# umodular_iface8_rev01.net
KiCad netlist of a schematic drawn in EAGLE
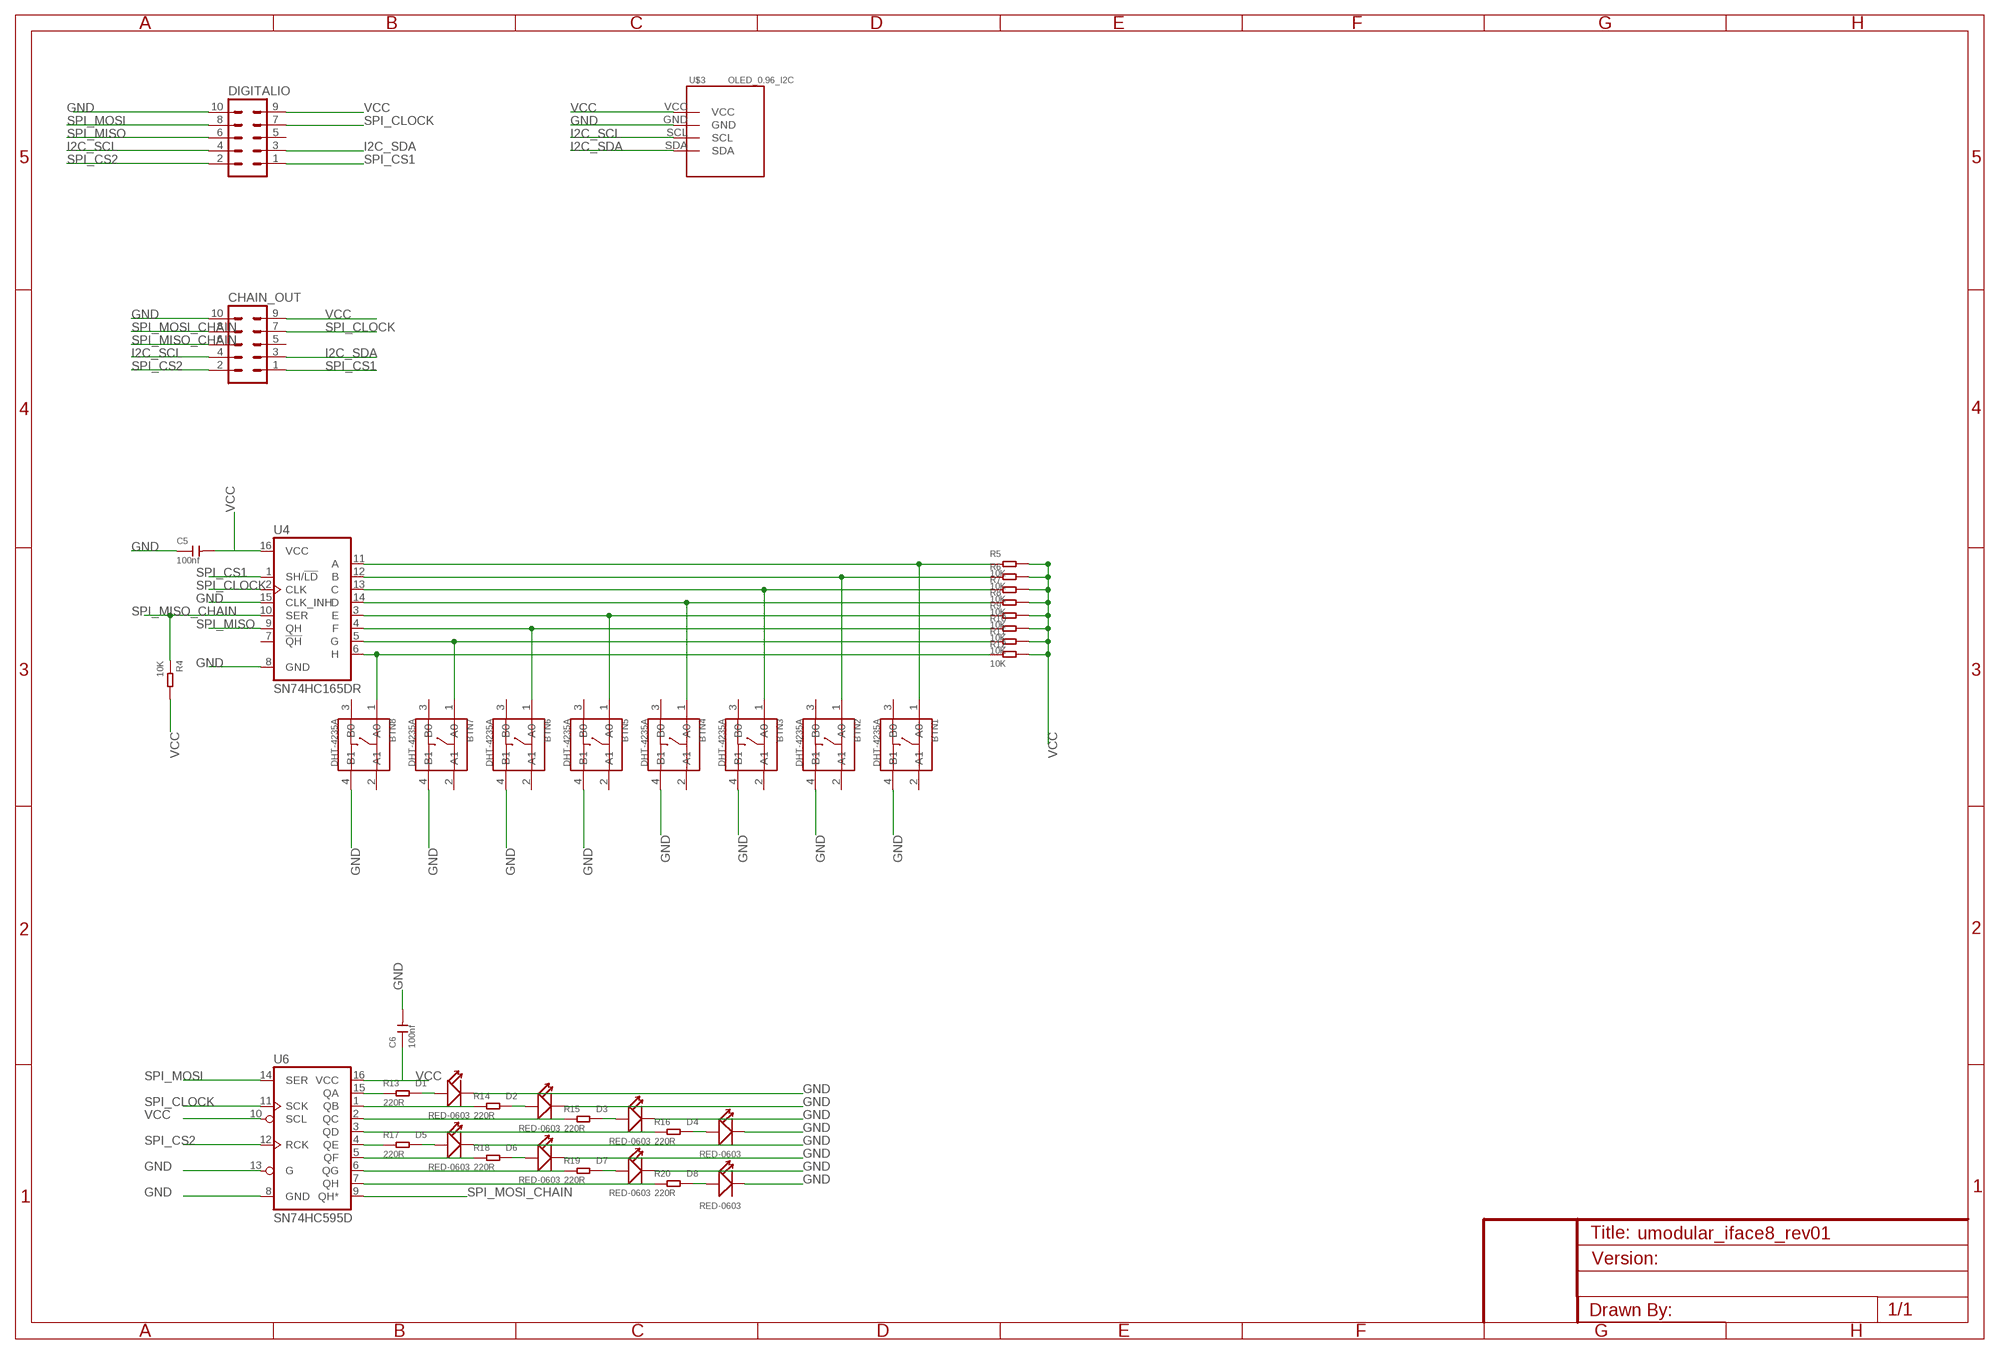
[diagram p0: schematic, sheet 1]

(export (version "E")
  (design (tool "Eeschema 10.0.6"))
  (components
    (comp (ref "BTN1")
      (value "DHT-4235A")
      (footprint "eagle-import:SW4-SMD-4.2X3.2X2.5MM")
      (libsource (lib "eagle-import") (part "SMD-BUTTON-TOP-DHT-4235A(4P-4.2X3.2MM)"))
    )
    (comp (ref "BTN2")
      (value "DHT-4235A")
      (footprint "eagle-import:SW4-SMD-4.2X3.2X2.5MM")
      (libsource (lib "eagle-import") (part "SMD-BUTTON-TOP-DHT-4235A(4P-4.2X3.2MM)"))
    )
    (comp (ref "BTN3")
      (value "DHT-4235A")
      (footprint "eagle-import:SW4-SMD-4.2X3.2X2.5MM")
      (libsource (lib "eagle-import") (part "SMD-BUTTON-TOP-DHT-4235A(4P-4.2X3.2MM)"))
    )
    (comp (ref "BTN4")
      (value "DHT-4235A")
      (footprint "eagle-import:SW4-SMD-4.2X3.2X2.5MM")
      (libsource (lib "eagle-import") (part "SMD-BUTTON-TOP-DHT-4235A(4P-4.2X3.2MM)"))
    )
    (comp (ref "BTN5")
      (value "DHT-4235A")
      (footprint "eagle-import:SW4-SMD-4.2X3.2X2.5MM")
      (libsource (lib "eagle-import") (part "SMD-BUTTON-TOP-DHT-4235A(4P-4.2X3.2MM)"))
    )
    (comp (ref "BTN6")
      (value "DHT-4235A")
      (footprint "eagle-import:SW4-SMD-4.2X3.2X2.5MM")
      (libsource (lib "eagle-import") (part "SMD-BUTTON-TOP-DHT-4235A(4P-4.2X3.2MM)"))
    )
    (comp (ref "BTN7")
      (value "DHT-4235A")
      (footprint "eagle-import:SW4-SMD-4.2X3.2X2.5MM")
      (libsource (lib "eagle-import") (part "SMD-BUTTON-TOP-DHT-4235A(4P-4.2X3.2MM)"))
    )
    (comp (ref "BTN8")
      (value "DHT-4235A")
      (footprint "eagle-import:SW4-SMD-4.2X3.2X2.5MM")
      (libsource (lib "eagle-import") (part "SMD-BUTTON-TOP-DHT-4235A(4P-4.2X3.2MM)"))
    )
    (comp (ref "C5")
      (value "100nf")
      (footprint "eagle-import:C0805")
      (fields (field (name "MPN") "CC0805KRX7R9BB104"))
      (libsource (lib "eagle-import") (part "CERAMIC-100NF-50V-10%-X7R(0805)"))
    )
    (comp (ref "C6")
      (value "100nf")
      (footprint "eagle-import:C0805")
      (fields (field (name "MPN") "CC0805KRX7R9BB104"))
      (libsource (lib "eagle-import") (part "CERAMIC-100NF-50V-10%-X7R(0805)"))
    )
    (comp (ref "CHAIN_OUT")
      (value "MA05-2")
      (footprint "eagle-import:MA05-2")
      (libsource (lib "eagle-import") (part "MA05-2"))
    )
    (comp (ref "D1")
      (value "RED-0603")
      (footprint "eagle-import:LED-0603")
      (fields (field (name "MPN") "19-217-R6C-AL1M2VY-3T"))
      (libsource (lib "eagle-import") (part "LED-SMD-RED-DIFFUSED(0603)"))
    )
    (comp (ref "D2")
      (value "RED-0603")
      (footprint "eagle-import:LED-0603")
      (fields (field (name "MPN") "19-217-R6C-AL1M2VY-3T"))
      (libsource (lib "eagle-import") (part "LED-SMD-RED-DIFFUSED(0603)"))
    )
    (comp (ref "D3")
      (value "RED-0603")
      (footprint "eagle-import:LED-0603")
      (fields (field (name "MPN") "19-217-R6C-AL1M2VY-3T"))
      (libsource (lib "eagle-import") (part "LED-SMD-RED-DIFFUSED(0603)"))
    )
    (comp (ref "D4")
      (value "RED-0603")
      (footprint "eagle-import:LED-0603")
      (fields (field (name "MPN") "19-217-R6C-AL1M2VY-3T"))
      (libsource (lib "eagle-import") (part "LED-SMD-RED-DIFFUSED(0603)"))
    )
    (comp (ref "D5")
      (value "RED-0603")
      (footprint "eagle-import:LED-0603")
      (fields (field (name "MPN") "19-217-R6C-AL1M2VY-3T"))
      (libsource (lib "eagle-import") (part "LED-SMD-RED-DIFFUSED(0603)"))
    )
    (comp (ref "D6")
      (value "RED-0603")
      (footprint "eagle-import:LED-0603")
      (fields (field (name "MPN") "19-217-R6C-AL1M2VY-3T"))
      (libsource (lib "eagle-import") (part "LED-SMD-RED-DIFFUSED(0603)"))
    )
    (comp (ref "D7")
      (value "RED-0603")
      (footprint "eagle-import:LED-0603")
      (fields (field (name "MPN") "19-217-R6C-AL1M2VY-3T"))
      (libsource (lib "eagle-import") (part "LED-SMD-RED-DIFFUSED(0603)"))
    )
    (comp (ref "D8")
      (value "RED-0603")
      (footprint "eagle-import:LED-0603")
      (fields (field (name "MPN") "19-217-R6C-AL1M2VY-3T"))
      (libsource (lib "eagle-import") (part "LED-SMD-RED-DIFFUSED(0603)"))
    )
    (comp (ref "DIGITALIO")
      (value "MA05-2")
      (footprint "eagle-import:MA05-2")
      (libsource (lib "eagle-import") (part "MA05-2"))
    )
    (comp (ref "R4")
      (value "10K")
      (footprint "eagle-import:R0603")
      (fields (field (name "MPN") "RC0603JR-0710KL"))
      (libsource (lib "eagle-import") (part "SMD-RES-10K-5%-1/10W(0603)"))
    )
    (comp (ref "R5")
      (value "10K")
      (footprint "eagle-import:R0603")
      (fields (field (name "MPN") "RC0603JR-0710KL"))
      (libsource (lib "eagle-import") (part "SMD-RES-10K-5%-1/10W(0603)"))
    )
    (comp (ref "R6")
      (value "10K")
      (footprint "eagle-import:R0603")
      (fields (field (name "MPN") "RC0603JR-0710KL"))
      (libsource (lib "eagle-import") (part "SMD-RES-10K-5%-1/10W(0603)"))
    )
    (comp (ref "R7")
      (value "10K")
      (footprint "eagle-import:R0603")
      (fields (field (name "MPN") "RC0603JR-0710KL"))
      (libsource (lib "eagle-import") (part "SMD-RES-10K-5%-1/10W(0603)"))
    )
    (comp (ref "R8")
      (value "10K")
      (footprint "eagle-import:R0603")
      (fields (field (name "MPN") "RC0603JR-0710KL"))
      (libsource (lib "eagle-import") (part "SMD-RES-10K-5%-1/10W(0603)"))
    )
    (comp (ref "R9")
      (value "10K")
      (footprint "eagle-import:R0603")
      (fields (field (name "MPN") "RC0603JR-0710KL"))
      (libsource (lib "eagle-import") (part "SMD-RES-10K-5%-1/10W(0603)"))
    )
    (comp (ref "R10")
      (value "10K")
      (footprint "eagle-import:R0603")
      (fields (field (name "MPN") "RC0603JR-0710KL"))
      (libsource (lib "eagle-import") (part "SMD-RES-10K-5%-1/10W(0603)"))
    )
    (comp (ref "R11")
      (value "10K")
      (footprint "eagle-import:R0603")
      (fields (field (name "MPN") "RC0603JR-0710KL"))
      (libsource (lib "eagle-import") (part "SMD-RES-10K-5%-1/10W(0603)"))
    )
    (comp (ref "R12")
      (value "10K")
      (footprint "eagle-import:R0603")
      (fields (field (name "MPN") "RC0603JR-0710KL"))
      (libsource (lib "eagle-import") (part "SMD-RES-10K-5%-1/10W(0603)"))
    )
    (comp (ref "R13")
      (value "220R")
      (footprint "eagle-import:R0603")
      (fields (field (name "MPN") "RC0603JR-07220RL"))
      (libsource (lib "eagle-import") (part "SMD-RES-220R-5%-1/10W(0603)"))
    )
    (comp (ref "R14")
      (value "220R")
      (footprint "eagle-import:R0603")
      (fields (field (name "MPN") "RC0603JR-07220RL"))
      (libsource (lib "eagle-import") (part "SMD-RES-220R-5%-1/10W(0603)"))
    )
    (comp (ref "R15")
      (value "220R")
      (footprint "eagle-import:R0603")
      (fields (field (name "MPN") "RC0603JR-07220RL"))
      (libsource (lib "eagle-import") (part "SMD-RES-220R-5%-1/10W(0603)"))
    )
    (comp (ref "R16")
      (value "220R")
      (footprint "eagle-import:R0603")
      (fields (field (name "MPN") "RC0603JR-07220RL"))
      (libsource (lib "eagle-import") (part "SMD-RES-220R-5%-1/10W(0603)"))
    )
    (comp (ref "R17")
      (value "220R")
      (footprint "eagle-import:R0603")
      (fields (field (name "MPN") "RC0603JR-07220RL"))
      (libsource (lib "eagle-import") (part "SMD-RES-220R-5%-1/10W(0603)"))
    )
    (comp (ref "R18")
      (value "220R")
      (footprint "eagle-import:R0603")
      (fields (field (name "MPN") "RC0603JR-07220RL"))
      (libsource (lib "eagle-import") (part "SMD-RES-220R-5%-1/10W(0603)"))
    )
    (comp (ref "R19")
      (value "220R")
      (footprint "eagle-import:R0603")
      (fields (field (name "MPN") "RC0603JR-07220RL"))
      (libsource (lib "eagle-import") (part "SMD-RES-220R-5%-1/10W(0603)"))
    )
    (comp (ref "R20")
      (value "220R")
      (footprint "eagle-import:R0603")
      (fields (field (name "MPN") "RC0603JR-07220RL"))
      (libsource (lib "eagle-import") (part "SMD-RES-220R-5%-1/10W(0603)"))
    )
    (comp (ref "U$3")
      (value "OLED_0.96_I2C")
      (footprint "eagle-import:OLED_0.96_I2C")
      (libsource (lib "eagle-import") (part "OLED_0.96_I2C"))
    )
    (comp (ref "U4")
      (value "SN74HC165DR")
      (footprint "eagle-import:SO16")
      (libsource (lib "eagle-import") (part "74165DHC"))
    )
    (comp (ref "U6")
      (value "SN74HC595D")
      (footprint "eagle-import:SO16")
      (libsource (lib "eagle-import") (part "74595DHC"))
    )
  )
  (nets
    (net (code "1") (name "/GND") (class "Default")
      (node (ref "BTN1") (pin "4") (pinfunction "B1_4") (pintype "bidirectional"))
      (node (ref "BTN2") (pin "4") (pinfunction "B1_4") (pintype "bidirectional"))
      (node (ref "BTN3") (pin "4") (pinfunction "B1_4") (pintype "bidirectional"))
      (node (ref "BTN4") (pin "4") (pinfunction "B1_4") (pintype "bidirectional"))
      (node (ref "BTN5") (pin "4") (pinfunction "B1_4") (pintype "bidirectional"))
      (node (ref "BTN6") (pin "4") (pinfunction "B1_4") (pintype "bidirectional"))
      (node (ref "BTN7") (pin "4") (pinfunction "B1_4") (pintype "bidirectional"))
      (node (ref "BTN8") (pin "4") (pinfunction "B1_4") (pintype "bidirectional"))
      (node (ref "C5") (pin "1") (pinfunction "1_1") (pintype "passive"))
      (node (ref "C6") (pin "2") (pinfunction "2_2") (pintype "passive"))
      (node (ref "CHAIN_OUT") (pin "10") (pinfunction "10_10") (pintype "passive"))
      (node (ref "D1") (pin "-") (pinfunction "-_-") (pintype "passive"))
      (node (ref "D2") (pin "-") (pinfunction "-_-") (pintype "passive"))
      (node (ref "D3") (pin "-") (pinfunction "-_-") (pintype "passive"))
      (node (ref "D4") (pin "-") (pinfunction "-_-") (pintype "passive"))
      (node (ref "D5") (pin "-") (pinfunction "-_-") (pintype "passive"))
      (node (ref "D6") (pin "-") (pinfunction "-_-") (pintype "passive"))
      (node (ref "D7") (pin "-") (pinfunction "-_-") (pintype "passive"))
      (node (ref "D8") (pin "-") (pinfunction "-_-") (pintype "passive"))
      (node (ref "DIGITALIO") (pin "10") (pinfunction "10_10") (pintype "passive"))
      (node (ref "U$3") (pin "GND") (pinfunction "GND_GND") (pintype "bidirectional"))
      (node (ref "U4") (pin "15") (pinfunction "CLK_INH_15") (pintype "input"))
      (node (ref "U4") (pin "8") (pinfunction "GND_8") (pintype "power_in"))
      (node (ref "U6") (pin "13") (pinfunction "G_13") (pintype "input"))
      (node (ref "U6") (pin "8") (pinfunction "GND_8") (pintype "power_in"))
    )
    (net (code "2") (name "/I2C_SCL") (class "Default")
      (node (ref "CHAIN_OUT") (pin "4") (pinfunction "4_4") (pintype "passive"))
      (node (ref "DIGITALIO") (pin "4") (pinfunction "4_4") (pintype "passive"))
      (node (ref "U$3") (pin "SCL") (pinfunction "SCL_SCL") (pintype "bidirectional"))
    )
    (net (code "3") (name "/I2C_SDA") (class "Default")
      (node (ref "CHAIN_OUT") (pin "3") (pinfunction "3_3") (pintype "passive"))
      (node (ref "DIGITALIO") (pin "3") (pinfunction "3_3") (pintype "passive"))
      (node (ref "U$3") (pin "SDA") (pinfunction "SDA_SDA") (pintype "bidirectional"))
    )
    (net (code "4") (name "/SPI_CLOCK") (class "Default")
      (node (ref "CHAIN_OUT") (pin "7") (pinfunction "7_7") (pintype "passive"))
      (node (ref "DIGITALIO") (pin "7") (pinfunction "7_7") (pintype "passive"))
      (node (ref "U4") (pin "2") (pinfunction "CLK_2") (pintype "input"))
      (node (ref "U6") (pin "11") (pinfunction "SCK_11") (pintype "input"))
    )
    (net (code "5") (name "/SPI_CS1") (class "Default")
      (node (ref "CHAIN_OUT") (pin "1") (pinfunction "1_1") (pintype "passive"))
      (node (ref "DIGITALIO") (pin "1") (pinfunction "1_1") (pintype "passive"))
      (node (ref "U4") (pin "1") (pinfunction "SH/~{LD}_1") (pintype "input"))
    )
    (net (code "6") (name "/SPI_CS2") (class "Default")
      (node (ref "CHAIN_OUT") (pin "2") (pinfunction "2_2") (pintype "passive"))
      (node (ref "DIGITALIO") (pin "2") (pinfunction "2_2") (pintype "passive"))
      (node (ref "U6") (pin "12") (pinfunction "RCK_12") (pintype "input"))
    )
    (net (code "7") (name "/SPI_MISO") (class "Default")
      (node (ref "DIGITALIO") (pin "6") (pinfunction "6_6") (pintype "passive"))
      (node (ref "U4") (pin "9") (pinfunction "QH_9") (pintype "tri_state"))
    )
    (net (code "8") (name "/SPI_MISO_CHAIN") (class "Default")
      (node (ref "CHAIN_OUT") (pin "6") (pinfunction "6_6") (pintype "passive"))
      (node (ref "R4") (pin "1") (pinfunction "1_1") (pintype "passive"))
      (node (ref "U4") (pin "10") (pinfunction "SER_10") (pintype "input"))
    )
    (net (code "9") (name "/SPI_MOSI") (class "Default")
      (node (ref "DIGITALIO") (pin "8") (pinfunction "8_8") (pintype "passive"))
      (node (ref "U6") (pin "14") (pinfunction "SER_14") (pintype "input"))
    )
    (net (code "10") (name "/SPI_MOSI_CHAIN") (class "Default")
      (node (ref "CHAIN_OUT") (pin "8") (pinfunction "8_8") (pintype "passive"))
      (node (ref "U6") (pin "9") (pinfunction "QH*_9") (pintype "tri_state"))
    )
    (net (code "11") (name "/VCC") (class "Default")
      (node (ref "C5") (pin "2") (pinfunction "2_2") (pintype "passive"))
      (node (ref "C6") (pin "1") (pinfunction "1_1") (pintype "passive"))
      (node (ref "CHAIN_OUT") (pin "9") (pinfunction "9_9") (pintype "passive"))
      (node (ref "DIGITALIO") (pin "9") (pinfunction "9_9") (pintype "passive"))
      (node (ref "R10") (pin "2") (pinfunction "2_2") (pintype "passive"))
      (node (ref "R11") (pin "2") (pinfunction "2_2") (pintype "passive"))
      (node (ref "R12") (pin "2") (pinfunction "2_2") (pintype "passive"))
      (node (ref "R4") (pin "2") (pinfunction "2_2") (pintype "passive"))
      (node (ref "R5") (pin "2") (pinfunction "2_2") (pintype "passive"))
      (node (ref "R6") (pin "2") (pinfunction "2_2") (pintype "passive"))
      (node (ref "R7") (pin "2") (pinfunction "2_2") (pintype "passive"))
      (node (ref "R8") (pin "2") (pinfunction "2_2") (pintype "passive"))
      (node (ref "R9") (pin "2") (pinfunction "2_2") (pintype "passive"))
      (node (ref "U$3") (pin "VCC") (pinfunction "VCC_VCC") (pintype "bidirectional"))
      (node (ref "U4") (pin "16") (pinfunction "VCC_16") (pintype "power_in"))
      (node (ref "U6") (pin "10") (pinfunction "SCL_10") (pintype "input"))
      (node (ref "U6") (pin "16") (pinfunction "VCC_16") (pintype "power_in"))
    )
    (net (code "12") (name "Net-(BTN1-A0)") (class "Default")
      (node (ref "BTN1") (pin "1") (pinfunction "A0_1") (pintype "bidirectional"))
      (node (ref "R5") (pin "1") (pinfunction "1_1") (pintype "passive"))
      (node (ref "U4") (pin "11") (pinfunction "A_11") (pintype "tri_state"))
    )
    (net (code "13") (name "Net-(BTN2-A0)") (class "Default")
      (node (ref "BTN2") (pin "1") (pinfunction "A0_1") (pintype "bidirectional"))
      (node (ref "R6") (pin "1") (pinfunction "1_1") (pintype "passive"))
      (node (ref "U4") (pin "12") (pinfunction "B_12") (pintype "tri_state"))
    )
    (net (code "14") (name "Net-(BTN3-A0)") (class "Default")
      (node (ref "BTN3") (pin "1") (pinfunction "A0_1") (pintype "bidirectional"))
      (node (ref "R7") (pin "1") (pinfunction "1_1") (pintype "passive"))
      (node (ref "U4") (pin "13") (pinfunction "C_13") (pintype "tri_state"))
    )
    (net (code "15") (name "Net-(BTN4-A0)") (class "Default")
      (node (ref "BTN4") (pin "1") (pinfunction "A0_1") (pintype "bidirectional"))
      (node (ref "R8") (pin "1") (pinfunction "1_1") (pintype "passive"))
      (node (ref "U4") (pin "14") (pinfunction "D_14") (pintype "tri_state"))
    )
    (net (code "16") (name "Net-(BTN5-A0)") (class "Default")
      (node (ref "BTN5") (pin "1") (pinfunction "A0_1") (pintype "bidirectional"))
      (node (ref "R9") (pin "1") (pinfunction "1_1") (pintype "passive"))
      (node (ref "U4") (pin "3") (pinfunction "E_3") (pintype "tri_state"))
    )
    (net (code "17") (name "Net-(BTN6-A0)") (class "Default")
      (node (ref "BTN6") (pin "1") (pinfunction "A0_1") (pintype "bidirectional"))
      (node (ref "R10") (pin "1") (pinfunction "1_1") (pintype "passive"))
      (node (ref "U4") (pin "4") (pinfunction "F_4") (pintype "tri_state"))
    )
    (net (code "18") (name "Net-(BTN7-A0)") (class "Default")
      (node (ref "BTN7") (pin "1") (pinfunction "A0_1") (pintype "bidirectional"))
      (node (ref "R11") (pin "1") (pinfunction "1_1") (pintype "passive"))
      (node (ref "U4") (pin "5") (pinfunction "G_5") (pintype "tri_state"))
    )
    (net (code "19") (name "Net-(BTN8-A0)") (class "Default")
      (node (ref "BTN8") (pin "1") (pinfunction "A0_1") (pintype "bidirectional"))
      (node (ref "R12") (pin "1") (pinfunction "1_1") (pintype "passive"))
      (node (ref "U4") (pin "6") (pinfunction "H_6") (pintype "tri_state"))
    )
    (net (code "20") (name "Net-(D1-Pad+)") (class "Default")
      (node (ref "D1") (pin "+") (pinfunction "+_+") (pintype "passive"))
      (node (ref "R13") (pin "2") (pinfunction "2_2") (pintype "passive"))
    )
    (net (code "21") (name "Net-(D2-Pad+)") (class "Default")
      (node (ref "D2") (pin "+") (pinfunction "+_+") (pintype "passive"))
      (node (ref "R14") (pin "2") (pinfunction "2_2") (pintype "passive"))
    )
    (net (code "22") (name "Net-(D3-Pad+)") (class "Default")
      (node (ref "D3") (pin "+") (pinfunction "+_+") (pintype "passive"))
      (node (ref "R15") (pin "2") (pinfunction "2_2") (pintype "passive"))
    )
    (net (code "23") (name "Net-(D4-Pad+)") (class "Default")
      (node (ref "D4") (pin "+") (pinfunction "+_+") (pintype "passive"))
      (node (ref "R16") (pin "2") (pinfunction "2_2") (pintype "passive"))
    )
    (net (code "24") (name "Net-(D5-Pad+)") (class "Default")
      (node (ref "D5") (pin "+") (pinfunction "+_+") (pintype "passive"))
      (node (ref "R17") (pin "2") (pinfunction "2_2") (pintype "passive"))
    )
    (net (code "25") (name "Net-(D6-Pad+)") (class "Default")
      (node (ref "D6") (pin "+") (pinfunction "+_+") (pintype "passive"))
      (node (ref "R18") (pin "2") (pinfunction "2_2") (pintype "passive"))
    )
    (net (code "26") (name "Net-(D7-Pad+)") (class "Default")
      (node (ref "D7") (pin "+") (pinfunction "+_+") (pintype "passive"))
      (node (ref "R19") (pin "2") (pinfunction "2_2") (pintype "passive"))
    )
    (net (code "27") (name "Net-(D8-Pad+)") (class "Default")
      (node (ref "D8") (pin "+") (pinfunction "+_+") (pintype "passive"))
      (node (ref "R20") (pin "2") (pinfunction "2_2") (pintype "passive"))
    )
    (net (code "28") (name "Net-(U6-QA)") (class "Default")
      (node (ref "R13") (pin "1") (pinfunction "1_1") (pintype "passive"))
      (node (ref "U6") (pin "15") (pinfunction "QA_15") (pintype "tri_state"))
    )
    (net (code "29") (name "Net-(U6-QB)") (class "Default")
      (node (ref "R14") (pin "1") (pinfunction "1_1") (pintype "passive"))
      (node (ref "U6") (pin "1") (pinfunction "QB_1") (pintype "tri_state"))
    )
    (net (code "30") (name "Net-(U6-QC)") (class "Default")
      (node (ref "R15") (pin "1") (pinfunction "1_1") (pintype "passive"))
      (node (ref "U6") (pin "2") (pinfunction "QC_2") (pintype "tri_state"))
    )
    (net (code "31") (name "Net-(U6-QD)") (class "Default")
      (node (ref "R16") (pin "1") (pinfunction "1_1") (pintype "passive"))
      (node (ref "U6") (pin "3") (pinfunction "QD_3") (pintype "tri_state"))
    )
    (net (code "32") (name "Net-(U6-QE)") (class "Default")
      (node (ref "R17") (pin "1") (pinfunction "1_1") (pintype "passive"))
      (node (ref "U6") (pin "4") (pinfunction "QE_4") (pintype "tri_state"))
    )
    (net (code "33") (name "Net-(U6-QF)") (class "Default")
      (node (ref "R18") (pin "1") (pinfunction "1_1") (pintype "passive"))
      (node (ref "U6") (pin "5") (pinfunction "QF_5") (pintype "tri_state"))
    )
    (net (code "34") (name "Net-(U6-QG)") (class "Default")
      (node (ref "R19") (pin "1") (pinfunction "1_1") (pintype "passive"))
      (node (ref "U6") (pin "6") (pinfunction "QG_6") (pintype "tri_state"))
    )
    (net (code "35") (name "Net-(U6-QH)") (class "Default")
      (node (ref "R20") (pin "1") (pinfunction "1_1") (pintype "passive"))
      (node (ref "U6") (pin "7") (pinfunction "QH_7") (pintype "tri_state"))
    )
    (net (code "36") (name "unconnected-(BTN1-A1-Pad2)") (class "Default")
      (node (ref "BTN1") (pin "2") (pinfunction "A1_2") (pintype "bidirectional"))
    )
    (net (code "37") (name "unconnected-(BTN1-B0-Pad3)") (class "Default")
      (node (ref "BTN1") (pin "3") (pinfunction "B0_3") (pintype "bidirectional"))
    )
    (net (code "38") (name "unconnected-(BTN2-A1-Pad2)") (class "Default")
      (node (ref "BTN2") (pin "2") (pinfunction "A1_2") (pintype "bidirectional"))
    )
    (net (code "39") (name "unconnected-(BTN2-B0-Pad3)") (class "Default")
      (node (ref "BTN2") (pin "3") (pinfunction "B0_3") (pintype "bidirectional"))
    )
    (net (code "40") (name "unconnected-(BTN3-A1-Pad2)") (class "Default")
      (node (ref "BTN3") (pin "2") (pinfunction "A1_2") (pintype "bidirectional"))
    )
    (net (code "41") (name "unconnected-(BTN3-B0-Pad3)") (class "Default")
      (node (ref "BTN3") (pin "3") (pinfunction "B0_3") (pintype "bidirectional"))
    )
    (net (code "42") (name "unconnected-(BTN4-A1-Pad2)") (class "Default")
      (node (ref "BTN4") (pin "2") (pinfunction "A1_2") (pintype "bidirectional"))
    )
    (net (code "43") (name "unconnected-(BTN4-B0-Pad3)") (class "Default")
      (node (ref "BTN4") (pin "3") (pinfunction "B0_3") (pintype "bidirectional"))
    )
    (net (code "44") (name "unconnected-(BTN5-A1-Pad2)") (class "Default")
      (node (ref "BTN5") (pin "2") (pinfunction "A1_2") (pintype "bidirectional"))
    )
    (net (code "45") (name "unconnected-(BTN5-B0-Pad3)") (class "Default")
      (node (ref "BTN5") (pin "3") (pinfunction "B0_3") (pintype "bidirectional"))
    )
    (net (code "46") (name "unconnected-(BTN6-A1-Pad2)") (class "Default")
      (node (ref "BTN6") (pin "2") (pinfunction "A1_2") (pintype "bidirectional"))
    )
    (net (code "47") (name "unconnected-(BTN6-B0-Pad3)") (class "Default")
      (node (ref "BTN6") (pin "3") (pinfunction "B0_3") (pintype "bidirectional"))
    )
    (net (code "48") (name "unconnected-(BTN7-A1-Pad2)") (class "Default")
      (node (ref "BTN7") (pin "2") (pinfunction "A1_2") (pintype "bidirectional"))
    )
    (net (code "49") (name "unconnected-(BTN7-B0-Pad3)") (class "Default")
      (node (ref "BTN7") (pin "3") (pinfunction "B0_3") (pintype "bidirectional"))
    )
    (net (code "50") (name "unconnected-(BTN8-A1-Pad2)") (class "Default")
      (node (ref "BTN8") (pin "2") (pinfunction "A1_2") (pintype "bidirectional"))
    )
    (net (code "51") (name "unconnected-(BTN8-B0-Pad3)") (class "Default")
      (node (ref "BTN8") (pin "3") (pinfunction "B0_3") (pintype "bidirectional"))
    )
    (net (code "52") (name "unconnected-(CHAIN_OUT-Pad5)") (class "Default")
      (node (ref "CHAIN_OUT") (pin "5") (pinfunction "5_5") (pintype "passive"))
    )
    (net (code "53") (name "unconnected-(DIGITALIO-Pad5)") (class "Default")
      (node (ref "DIGITALIO") (pin "5") (pinfunction "5_5") (pintype "passive"))
    )
    (net (code "54") (name "unconnected-(U4-~{QH}-Pad7)") (class "Default")
      (node (ref "U4") (pin "7") (pinfunction "~{QH}_7") (pintype "input"))
    )
  )
)
